# Controller_Top_Sheet.net
KiCad netlist of a schematic drawn in Altium Designer
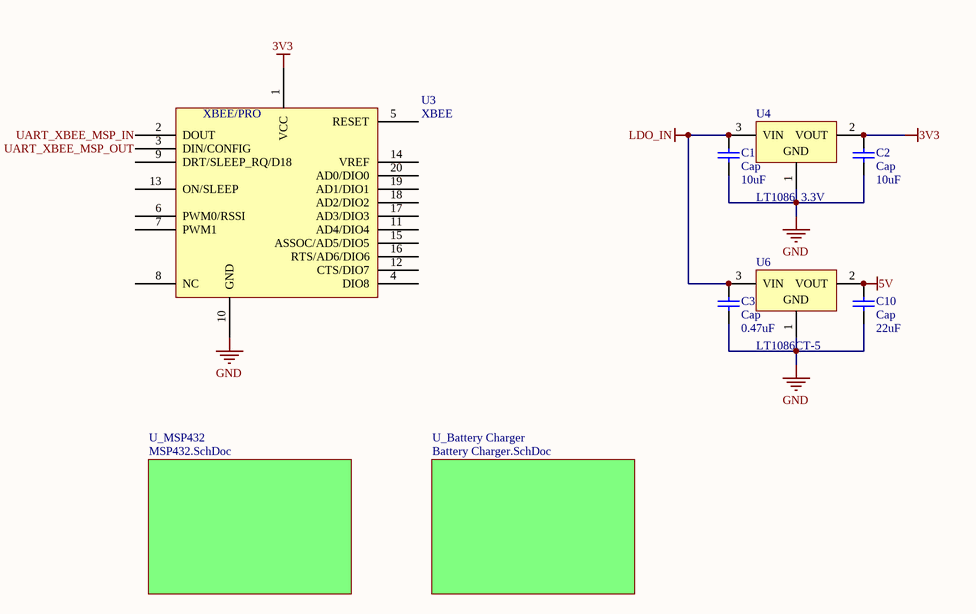
[diagram p0: Controller Top Sheet.SchDoc]

(export (version "E")
  (design (tool "Eeschema 10.0.6"))
  (components
    (comp (ref "C1")
      (value "Cap")
      (footprint "RAD-0.3")
      (description "Capacitor")
      (fields (field (name "ALTIUM_VALUE") "10uF") (field (name "PUBLISHER") "Altium Limited"))
      (libsource (lib "Miscellaneous Devices") (part "Cap"))
    )
    (comp (ref "C2")
      (value "Cap")
      (footprint "RAD-0.3")
      (description "Capacitor")
      (fields (field (name "ALTIUM_VALUE") "10uF") (field (name "PUBLISHER") "Altium Limited"))
      (libsource (lib "Miscellaneous Devices") (part "Cap"))
    )
    (comp (ref "C3")
      (value "Cap")
      (footprint "RAD-0.3")
      (description "Capacitor")
      (fields (field (name "ALTIUM_VALUE") "0.47uF") (field (name "PUBLISHER") "Altium Limited"))
      (libsource (lib "Miscellaneous Devices") (part "Cap"))
    )
    (comp (ref "C10")
      (value "Cap")
      (footprint "RAD-0.3")
      (description "Capacitor")
      (fields (field (name "ALTIUM_VALUE") "22uF") (field (name "PUBLISHER") "Altium Limited"))
      (libsource (lib "Miscellaneous Devices") (part "Cap"))
    )
    (comp (ref "U3") (value "XBEE") (footprint "XBEE/PRO") (libsource (lib "ECE LIB new") (part "XBEE")))
    (comp (ref "U4")
      (value "LT1086  3.3V")
      (footprint "TO-220")
      (libsource (lib "ECE LIB new") (part "LT1086  3.3V"))
    )
    (comp (ref "U6")
      (value "LT1086CT-5")
      (footprint "LT-T-3")
      (description "1.5 A Low Dropout Positive Regulator, 2.55 to 25 V Vin, 5 V Vout, 3-pin FM (T-3), 0 to 150 degC")
      (fields (field (name "MANUFACTURER") "Linear Technology"))
      (libsource (lib "ECE LIB new") (part "LT1086CT-5"))
    )
  )
  (nets
    (net (code "1") (name "/UART_XBEE_MSP_IN") (class "Default")
      (node (ref "U3") (pin "2") (pinfunction "DOUT_2") (pintype "passive"))
    )
    (net (code "2") (name "/UART_XBEE_MSP_OUT") (class "Default")
      (node (ref "U3") (pin "3") (pinfunction "DIN/CONFIG_3") (pintype "passive"))
    )
    (net (code "3") (name "3V3") (class "Default")
      (node (ref "C2") (pin "2") (pinfunction "2_2") (pintype "passive"))
      (node (ref "U3") (pin "1") (pinfunction "VCC_1") (pintype "passive"))
      (node (ref "U4") (pin "2") (pinfunction "VOUT_2") (pintype "power_in"))
    )
    (net (code "4") (name "5V") (class "Default")
      (node (ref "C10") (pin "2") (pinfunction "2_2") (pintype "passive"))
      (node (ref "U6") (pin "2") (pinfunction "VOUT_2") (pintype "power_in"))
    )
    (net (code "5") (name "GND") (class "Default")
      (node (ref "C1") (pin "1") (pinfunction "1_1") (pintype "passive"))
      (node (ref "C10") (pin "1") (pinfunction "1_1") (pintype "passive"))
      (node (ref "C2") (pin "1") (pinfunction "1_1") (pintype "passive"))
      (node (ref "C3") (pin "1") (pinfunction "1_1") (pintype "passive"))
      (node (ref "U3") (pin "10") (pinfunction "GND_10") (pintype "passive"))
      (node (ref "U4") (pin "1") (pinfunction "GND_1") (pintype "power_in"))
      (node (ref "U6") (pin "1") (pinfunction "GND_1") (pintype "power_in"))
    )
    (net (code "6") (name "LDO_IN") (class "Default")
      (node (ref "C1") (pin "2") (pinfunction "2_2") (pintype "passive"))
      (node (ref "C3") (pin "2") (pinfunction "2_2") (pintype "passive"))
      (node (ref "U4") (pin "3") (pinfunction "VIN_3") (pintype "power_in"))
      (node (ref "U6") (pin "3") (pinfunction "VIN_3") (pintype "power_in"))
    )
    (net (code "7") (name "unconnected-(U3-AD0{slash}DIO0-Pad20)") (class "Default")
      (node (ref "U3") (pin "20") (pinfunction "AD0/DIO0_20") (pintype "passive"))
    )
    (net (code "8") (name "unconnected-(U3-AD1{slash}DIO1-Pad19)") (class "Default")
      (node (ref "U3") (pin "19") (pinfunction "AD1/DIO1_19") (pintype "passive"))
    )
    (net (code "9") (name "unconnected-(U3-AD2{slash}DIO2-Pad18)") (class "Default")
      (node (ref "U3") (pin "18") (pinfunction "AD2/DIO2_18") (pintype "passive"))
    )
    (net (code "10") (name "unconnected-(U3-AD3{slash}DIO3-Pad17)") (class "Default")
      (node (ref "U3") (pin "17") (pinfunction "AD3/DIO3_17") (pintype "passive"))
    )
    (net (code "11") (name "unconnected-(U3-AD4{slash}DIO4-Pad11)") (class "Default")
      (node (ref "U3") (pin "11") (pinfunction "AD4/DIO4_11") (pintype "passive"))
    )
    (net (code "12") (name "unconnected-(U3-ASSOC{slash}AD5{slash}DIO5-Pad15)") (class "Default")
      (node (ref "U3") (pin "15") (pinfunction "ASSOC/AD5/DIO5_15") (pintype "passive"))
    )
    (net (code "13") (name "unconnected-(U3-CTS{slash}DIO7-Pad12)") (class "Default")
      (node (ref "U3") (pin "12") (pinfunction "CTS/DIO7_12") (pintype "passive"))
    )
    (net (code "14") (name "unconnected-(U3-DIO8-Pad4)") (class "Default")
      (node (ref "U3") (pin "4") (pinfunction "DIO8_4") (pintype "passive"))
    )
    (net (code "15") (name "unconnected-(U3-DRT{slash}SLEEP_RQ{slash}D18-Pad9)") (class "Default")
      (node (ref "U3") (pin "9") (pinfunction "DRT/SLEEP_RQ/D18_9") (pintype "passive"))
    )
    (net (code "16") (name "unconnected-(U3-NC-Pad8)") (class "Default")
      (node (ref "U3") (pin "8") (pinfunction "NC_8") (pintype "passive"))
    )
    (net (code "17") (name "unconnected-(U3-ON{slash}SLEEP-Pad13)") (class "Default")
      (node (ref "U3") (pin "13") (pinfunction "ON/SLEEP_13") (pintype "passive"))
    )
    (net (code "18") (name "unconnected-(U3-PWM0{slash}RSSI-Pad6)") (class "Default")
      (node (ref "U3") (pin "6") (pinfunction "PWM0/RSSI_6") (pintype "passive"))
    )
    (net (code "19") (name "unconnected-(U3-PWM1-Pad7)") (class "Default")
      (node (ref "U3") (pin "7") (pinfunction "PWM1_7") (pintype "passive"))
    )
    (net (code "20") (name "unconnected-(U3-RESET-Pad5)") (class "Default")
      (node (ref "U3") (pin "5") (pinfunction "RESET_5") (pintype "passive"))
    )
    (net (code "21") (name "unconnected-(U3-RTS{slash}AD6{slash}DIO6-Pad16)") (class "Default")
      (node (ref "U3") (pin "16") (pinfunction "RTS/AD6/DIO6_16") (pintype "passive"))
    )
    (net (code "22") (name "unconnected-(U3-VREF-Pad14)") (class "Default")
      (node (ref "U3") (pin "14") (pinfunction "VREF_14") (pintype "passive"))
    )
  )
)
